# SCH_SLV262-__2026-06-26.net
KiCad netlist of a schematic drawn in EasyEDA
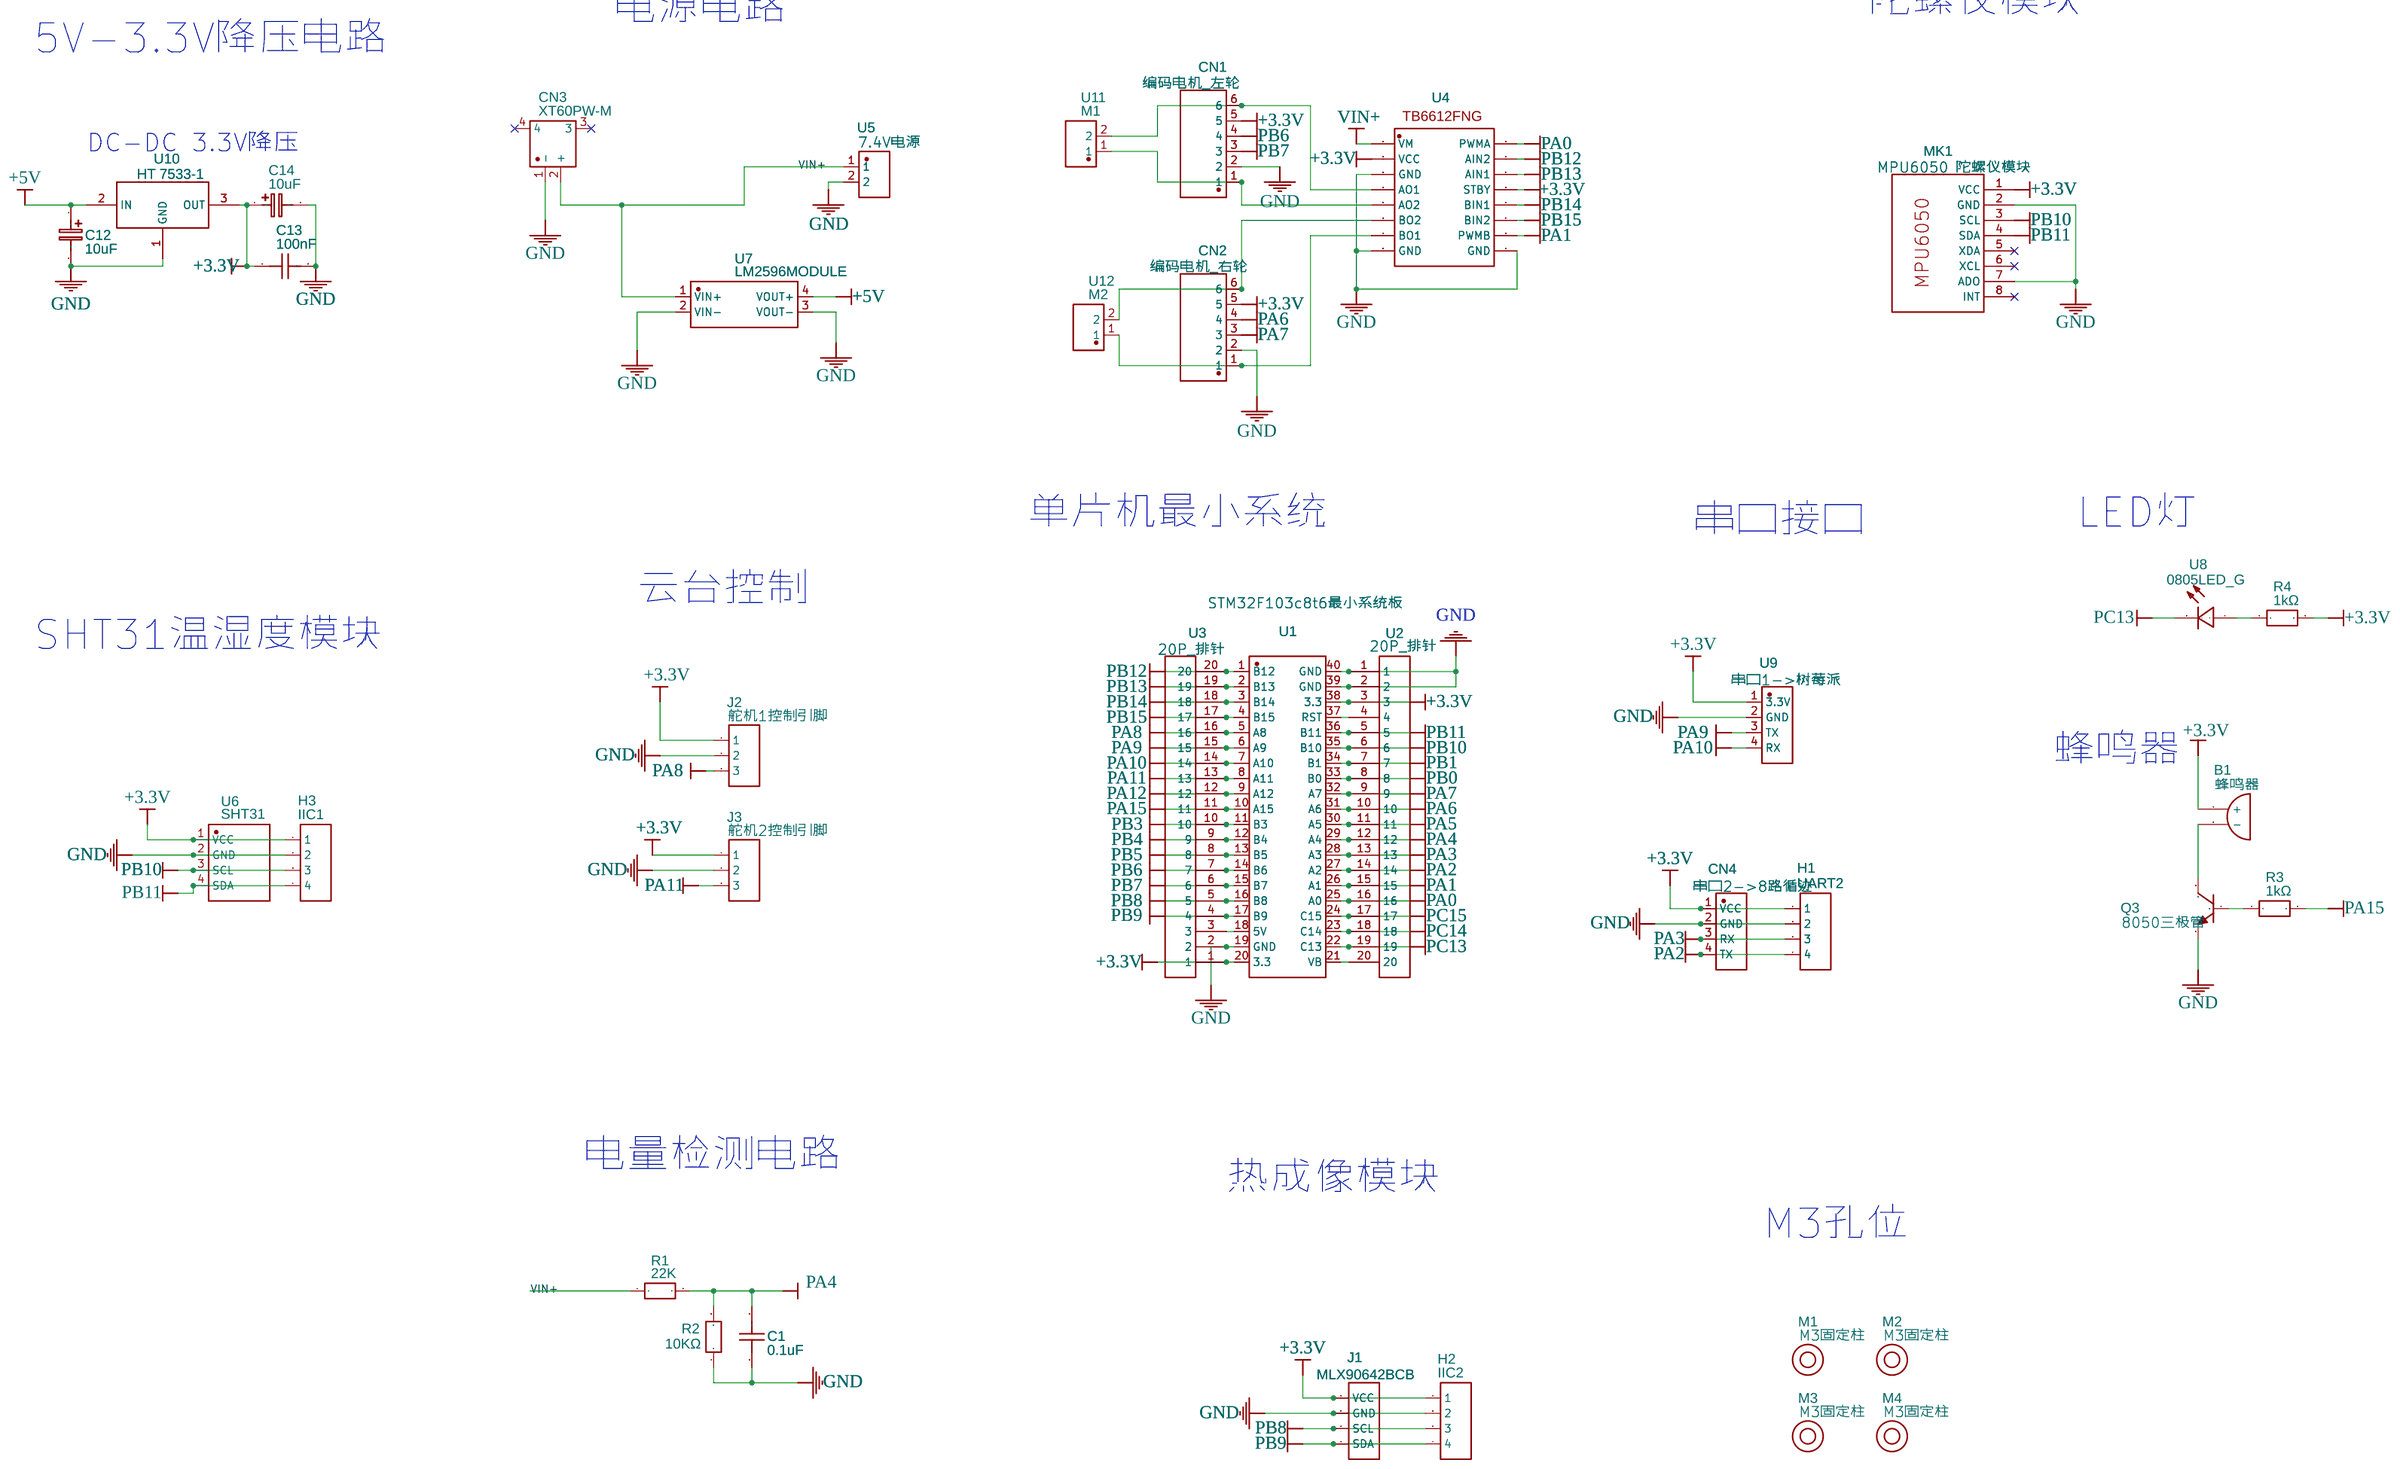
[diagram p0: schematic sheet]

(export (version "E")
  (design (tool "Eeschema 10.0.6"))
  (components
    (comp (ref "B1") (value "蜂鸣器") (libsource (lib "") (part "蜂鸣器")))
    (comp (ref "C1") (value "0.1uF") (libsource (lib "") (part "C_0603_US")))
    (comp (ref "C12") (value "10uF") (libsource (lib "") (part "C_Tan_SMD_A_EU_1")))
    (comp (ref "C13") (value "100nF") (libsource (lib "") (part "C_0603_US_1")))
    (comp (ref "C14") (value "10uF") (libsource (lib "") (part "C_Tan_SMD_A_EU")))
    (comp (ref "CN1")
      (value "编码电机_左轮")
      (fields (field (name "Manufacturer Part") "A2501WV-6P") (field (name "Manufacturer") "CJT(长江连接器)"))
      (libsource (lib "") (part "A2501WV-6P"))
    )
    (comp (ref "CN2")
      (value "编码电机_右轮")
      (fields (field (name "Manufacturer Part") "A2501WV-6P") (field (name "Manufacturer") "CJT(长江连接器)"))
      (libsource (lib "") (part "A2501WV-6P"))
    )
    (comp (ref "CN3")
      (value "XT60PW-M")
      (fields (field (name "Manufacturer") "AMASS(艾迈斯)"))
      (libsource (lib "") (part "XT60PW-M"))
    )
    (comp (ref "CN4")
      (value "串口2->8路循迹")
      (fields (field (name "Manufacturer Part") "HX-PH2.0-4PWZ") (field (name "Manufacturer") "hanxia(韩下)"))
      (libsource (lib "") (part "HX-PH2.0-4PWZ"))
    )
    (comp (ref "H1") (value "UART2") (libsource (lib "") (part "HDR-F-2.54_1x4")))
    (comp (ref "H2") (value "IIC2") (libsource (lib "") (part "HDR-F-2.54_1x4")))
    (comp (ref "H3") (value "IIC1") (libsource (lib "") (part "HDR-F-2.54_1x4")))
    (comp (ref "J1") (value "MLX90642BCB") (libsource (lib "") (part "HDR-M-2.54_1x4")))
    (comp (ref "J2") (value "舵机1控制引脚") (libsource (lib "") (part "HDR-M-2.54_1x3")))
    (comp (ref "J3") (value "舵机2控制引脚") (libsource (lib "") (part "HDR-M-2.54_1x3")))
    (comp (ref "M1") (value "M3固定柱") (libsource (lib "") (part "M3固定柱")))
    (comp (ref "M2") (value "M3固定柱") (libsource (lib "") (part "M3固定柱")))
    (comp (ref "M3") (value "M3固定柱") (libsource (lib "") (part "M3固定柱")))
    (comp (ref "M4") (value "M3固定柱") (libsource (lib "") (part "M3固定柱")))
    (comp (ref "MK1") (value "MPU6050 陀螺仪模块") (libsource (lib "") (part "MPU6050 陀螺仪模块")))
    (comp (ref "Q3")
      (value "8050三极管")
      (fields (field (name "Manufacturer Part") "SS8050DTA") (field (name "Manufacturer") "onsemi(安森美)"))
      (libsource (lib "") (part "8050三极管"))
    )
    (comp (ref "R1") (value "22K") (libsource (lib "") (part "R_0805_EU")))
    (comp (ref "R2") (value "10KΩ") (libsource (lib "") (part "R_0805_EU_1")))
    (comp (ref "R3")
      (value "1kΩ")
      (fields (field (name "Manufacturer Part") "PTFR0603B44K2N9") (field (name "Manufacturer") "RESI(开步睿思)"))
      (libsource (lib "") (part "R0603电阻"))
    )
    (comp (ref "R4")
      (value "1kΩ")
      (fields (field (name "Manufacturer Part") "PTFR0603B44K2N9") (field (name "Manufacturer") "RESI(开步睿思)"))
      (libsource (lib "") (part "R0603电阻"))
    )
    (comp (ref "U1") (value "STM32F103c8t6最小系统板") (libsource (lib "") (part "STM32F103c8t6最小系统板")))
    (comp (ref "U2") (value "20P_排针") (libsource (lib "") (part "20P排针")))
    (comp (ref "U3") (value "20P_排针") (libsource (lib "") (part "20P排针_1")))
    (comp (ref "U4") (value "TB6612") (libsource (lib "") (part "TB6612")))
    (comp (ref "U5")
      (value "7.4V电源")
      (fields (field (name "Manufacturer Part") "KF301-5.0-2P") (field (name "Manufacturer") "KEFA(科发)"))
      (libsource (lib "") (part "KF301-5.0-2P_1"))
    )
    (comp (ref "U6") (value "SHT31") (libsource (lib "") (part "SHT31")))
    (comp (ref "U7") (value "LM2596MODULE") (libsource (lib "") (part "LM2596MODULE")))
    (comp (ref "U8") (value "0805LED_G") (libsource (lib "") (part "0805LED_G")))
    (comp (ref "U9")
      (value "串口1->树莓派")
      (fields (field (name "Manufacturer Part") "XH2.54-4P- 直插"))
      (libsource (lib "") (part "XH2.54-4P- 直插"))
    )
    (comp (ref "U10") (value "HT 7533-1") (libsource (lib "") (part "HT 7533-1")))
    (comp (ref "U11")
      (value "M1")
      (fields (field (name "Manufacturer Part") "KF301-5.0-2P") (field (name "Manufacturer") "KEFA(科发)"))
      (libsource (lib "") (part "KF301-5.0-2P"))
    )
    (comp (ref "U12")
      (value "M2")
      (fields (field (name "Manufacturer Part") "KF301-5.0-2P") (field (name "Manufacturer") "KEFA(科发)"))
      (libsource (lib "") (part "KF301-5.0-2P"))
    )
  )
  (nets
    (net (code "1") (name "+3.3V") (class "Default")
      (node (ref "B1") (pin "1") (pinfunction "+_1") (pintype "unspecified"))
      (node (ref "C13") (pin "1") (pinfunction "1_1") (pintype "unspecified"))
      (node (ref "C14") (pin "1") (pinfunction "1_1") (pintype "unspecified"))
      (node (ref "CN1") (pin "5") (pinfunction "5_5") (pintype "unspecified"))
      (node (ref "CN2") (pin "5") (pinfunction "5_5") (pintype "unspecified"))
      (node (ref "CN4") (pin "1") (pinfunction "VCC_1") (pintype "unspecified"))
      (node (ref "H1") (pin "1") (pinfunction "1_1") (pintype "unspecified"))
      (node (ref "H2") (pin "1") (pinfunction "1_1") (pintype "unspecified"))
      (node (ref "H3") (pin "1") (pinfunction "1_1") (pintype "unspecified"))
      (node (ref "J1") (pin "1") (pinfunction "VCC_1") (pintype "unspecified"))
      (node (ref "J2") (pin "1") (pinfunction "1_1") (pintype "input"))
      (node (ref "J3") (pin "1") (pinfunction "1_1") (pintype "input"))
      (node (ref "MK1") (pin "1") (pinfunction "VCC_1") (pintype "unspecified"))
      (node (ref "R4") (pin "2") (pinfunction "2_2") (pintype "unspecified"))
      (node (ref "U1") (pin "20") (pinfunction "3.3_20") (pintype "unspecified"))
      (node (ref "U1") (pin "38") (pinfunction "3.3_38") (pintype "unspecified"))
      (node (ref "U10") (pin "3") (pinfunction "OUT_3") (pintype "unspecified"))
      (node (ref "U2") (pin "3") (pinfunction "3_3") (pintype "unspecified"))
      (node (ref "U3") (pin "1") (pinfunction "1_1") (pintype "unspecified"))
      (node (ref "U4") (pin "13") (pinfunction "STBY_13") (pintype "unspecified"))
      (node (ref "U4") (pin "2") (pinfunction "VCC_2") (pintype "unspecified"))
      (node (ref "U6") (pin "1") (pinfunction "VCC_1") (pintype "unspecified"))
      (node (ref "U9") (pin "1") (pinfunction "3.3V_1") (pintype "unspecified"))
    )
    (net (code "2") (name "+5V") (class "Default")
      (node (ref "C12") (pin "1") (pinfunction "1_1") (pintype "unspecified"))
      (node (ref "U10") (pin "2") (pinfunction "IN_2") (pintype "unspecified"))
      (node (ref "U7") (pin "4") (pinfunction "VOUT+_4") (pintype "unspecified"))
    )
    (net (code "3") (name "GND") (class "Default")
      (node (ref "C1") (pin "1") (pinfunction "1_1") (pintype "unspecified"))
      (node (ref "C12") (pin "2") (pinfunction "2_2") (pintype "unspecified"))
      (node (ref "C13") (pin "2") (pinfunction "2_2") (pintype "unspecified"))
      (node (ref "C14") (pin "2") (pinfunction "2_2") (pintype "unspecified"))
      (node (ref "CN1") (pin "2") (pinfunction "2_2") (pintype "unspecified"))
      (node (ref "CN2") (pin "2") (pinfunction "2_2") (pintype "unspecified"))
      (node (ref "CN3") (pin "1") (pinfunction "-_1") (pintype "unspecified"))
      (node (ref "CN4") (pin "2") (pinfunction "GND_2") (pintype "unspecified"))
      (node (ref "H1") (pin "2") (pinfunction "2_2") (pintype "unspecified"))
      (node (ref "H2") (pin "2") (pinfunction "2_2") (pintype "unspecified"))
      (node (ref "H3") (pin "2") (pinfunction "2_2") (pintype "unspecified"))
      (node (ref "J1") (pin "2") (pinfunction "GND_2") (pintype "unspecified"))
      (node (ref "J2") (pin "2") (pinfunction "2_2") (pintype "input"))
      (node (ref "J3") (pin "2") (pinfunction "2_2") (pintype "input"))
      (node (ref "MK1") (pin "2") (pinfunction "GND_2") (pintype "unspecified"))
      (node (ref "MK1") (pin "7") (pinfunction "ADO_7") (pintype "unspecified"))
      (node (ref "Q3") (pin "1") (pinfunction "E_1") (pintype "unspecified"))
      (node (ref "R2") (pin "1") (pinfunction "1_1") (pintype "unspecified"))
      (node (ref "U1") (pin "19") (pinfunction "GND_19") (pintype "unspecified"))
      (node (ref "U1") (pin "39") (pinfunction "GND_39") (pintype "unspecified"))
      (node (ref "U1") (pin "40") (pinfunction "GND_40") (pintype "unspecified"))
      (node (ref "U10") (pin "1") (pinfunction "GND_1") (pintype "unspecified"))
      (node (ref "U2") (pin "1") (pinfunction "1_1") (pintype "unspecified"))
      (node (ref "U2") (pin "2") (pinfunction "2_2") (pintype "unspecified"))
      (node (ref "U3") (pin "2") (pinfunction "2_2") (pintype "unspecified"))
      (node (ref "U4") (pin "3") (pinfunction "GND_3") (pintype "unspecified"))
      (node (ref "U4") (pin "8") (pinfunction "GND_8") (pintype "unspecified"))
      (node (ref "U4") (pin "9") (pinfunction "GND_9") (pintype "unspecified"))
      (node (ref "U5") (pin "2") (pinfunction "2_2") (pintype "unspecified"))
      (node (ref "U6") (pin "2") (pinfunction "GND_2") (pintype "unspecified"))
      (node (ref "U7") (pin "2") (pinfunction "VIN-_2") (pintype "unspecified"))
      (node (ref "U7") (pin "3") (pinfunction "VOUT-_3") (pintype "unspecified"))
      (node (ref "U9") (pin "2") (pinfunction "GND_2") (pintype "unspecified"))
    )
    (net (code "4") (name "Net-(B1--)") (class "Default")
      (node (ref "B1") (pin "2") (pinfunction "-_2") (pintype "unspecified"))
      (node (ref "Q3") (pin "3") (pinfunction "C_3") (pintype "unspecified"))
    )
    (net (code "5") (name "Net-(Q3-B)") (class "Default")
      (node (ref "Q3") (pin "2") (pinfunction "B_2") (pintype "unspecified"))
      (node (ref "R3") (pin "1") (pinfunction "1_1") (pintype "unspecified"))
    )
    (net (code "6") (name "Net-(U1-5V)") (class "Default")
      (node (ref "U1") (pin "18") (pinfunction "5V_18") (pintype "unspecified"))
      (node (ref "U3") (pin "3") (pinfunction "3_3") (pintype "unspecified"))
    )
    (net (code "7") (name "Net-(U1-RST)") (class "Default")
      (node (ref "U1") (pin "37") (pinfunction "RST_37") (pintype "unspecified"))
      (node (ref "U2") (pin "4") (pinfunction "4_4") (pintype "unspecified"))
    )
    (net (code "8") (name "Net-(U1-VB)") (class "Default")
      (node (ref "U1") (pin "21") (pinfunction "VB_21") (pintype "unspecified"))
      (node (ref "U2") (pin "20") (pinfunction "20_20") (pintype "unspecified"))
    )
    (net (code "9") (name "Net-(U4-AO1)") (class "Default")
      (node (ref "CN1") (pin "6") (pinfunction "6_6") (pintype "unspecified"))
      (node (ref "U11") (pin "2") (pinfunction "2_2") (pintype "unspecified"))
      (node (ref "U4") (pin "4") (pinfunction "AO1_4") (pintype "unspecified"))
    )
    (net (code "10") (name "Net-(U4-AO2)") (class "Default")
      (node (ref "CN1") (pin "1") (pinfunction "1_1") (pintype "unspecified"))
      (node (ref "U11") (pin "1") (pinfunction "1_1") (pintype "unspecified"))
      (node (ref "U4") (pin "5") (pinfunction "AO2_5") (pintype "unspecified"))
    )
    (net (code "11") (name "Net-(U4-BO1)") (class "Default")
      (node (ref "CN2") (pin "1") (pinfunction "1_1") (pintype "unspecified"))
      (node (ref "U12") (pin "1") (pinfunction "1_1") (pintype "unspecified"))
      (node (ref "U4") (pin "7") (pinfunction "BO1_7") (pintype "unspecified"))
    )
    (net (code "12") (name "Net-(U4-BO2)") (class "Default")
      (node (ref "CN2") (pin "6") (pinfunction "6_6") (pintype "unspecified"))
      (node (ref "U12") (pin "2") (pinfunction "2_2") (pintype "unspecified"))
      (node (ref "U4") (pin "6") (pinfunction "BO2_6") (pintype "unspecified"))
    )
    (net (code "13") (name "Net-(U8-+)") (class "Default")
      (node (ref "R4") (pin "1") (pinfunction "1_1") (pintype "unspecified"))
      (node (ref "U8") (pin "1") (pinfunction "+_1") (pintype "unspecified"))
    )
    (net (code "14") (name "PA0") (class "Default")
      (node (ref "U1") (pin "25") (pinfunction "A0_25") (pintype "unspecified"))
      (node (ref "U2") (pin "16") (pinfunction "16_16") (pintype "unspecified"))
      (node (ref "U4") (pin "16") (pinfunction "PWMA_16") (pintype "unspecified"))
    )
    (net (code "15") (name "PA1") (class "Default")
      (node (ref "U1") (pin "26") (pinfunction "A1_26") (pintype "unspecified"))
      (node (ref "U2") (pin "15") (pinfunction "15_15") (pintype "unspecified"))
      (node (ref "U4") (pin "10") (pinfunction "PWMB_10") (pintype "unspecified"))
    )
    (net (code "16") (name "PA2") (class "Default")
      (node (ref "CN4") (pin "4") (pinfunction "TX_4") (pintype "unspecified"))
      (node (ref "H1") (pin "4") (pinfunction "4_4") (pintype "unspecified"))
      (node (ref "U1") (pin "27") (pinfunction "A2_27") (pintype "unspecified"))
      (node (ref "U2") (pin "14") (pinfunction "14_14") (pintype "unspecified"))
    )
    (net (code "17") (name "PA3") (class "Default")
      (node (ref "CN4") (pin "3") (pinfunction "RX_3") (pintype "unspecified"))
      (node (ref "H1") (pin "3") (pinfunction "3_3") (pintype "unspecified"))
      (node (ref "U1") (pin "28") (pinfunction "A3_28") (pintype "unspecified"))
      (node (ref "U2") (pin "13") (pinfunction "13_13") (pintype "unspecified"))
    )
    (net (code "18") (name "PA4") (class "Default")
      (node (ref "C1") (pin "2") (pinfunction "2_2") (pintype "unspecified"))
      (node (ref "R1") (pin "2") (pinfunction "2_2") (pintype "unspecified"))
      (node (ref "R2") (pin "2") (pinfunction "2_2") (pintype "unspecified"))
      (node (ref "U1") (pin "29") (pinfunction "A4_29") (pintype "unspecified"))
      (node (ref "U2") (pin "12") (pinfunction "12_12") (pintype "unspecified"))
    )
    (net (code "19") (name "PA5") (class "Default")
      (node (ref "U1") (pin "30") (pinfunction "A5_30") (pintype "unspecified"))
      (node (ref "U2") (pin "11") (pinfunction "11_11") (pintype "unspecified"))
    )
    (net (code "20") (name "PA6") (class "Default")
      (node (ref "CN2") (pin "4") (pinfunction "4_4") (pintype "unspecified"))
      (node (ref "U1") (pin "31") (pinfunction "A6_31") (pintype "unspecified"))
      (node (ref "U2") (pin "10") (pinfunction "10_10") (pintype "unspecified"))
    )
    (net (code "21") (name "PA7") (class "Default")
      (node (ref "CN2") (pin "3") (pinfunction "3_3") (pintype "unspecified"))
      (node (ref "U1") (pin "32") (pinfunction "A7_32") (pintype "unspecified"))
      (node (ref "U2") (pin "9") (pinfunction "9_9") (pintype "unspecified"))
    )
    (net (code "22") (name "PA8") (class "Default")
      (node (ref "J2") (pin "3") (pinfunction "3_3") (pintype "input"))
      (node (ref "U1") (pin "5") (pinfunction "A8_5") (pintype "unspecified"))
      (node (ref "U3") (pin "16") (pinfunction "16_16") (pintype "unspecified"))
    )
    (net (code "23") (name "PA9") (class "Default")
      (node (ref "U1") (pin "6") (pinfunction "A9_6") (pintype "unspecified"))
      (node (ref "U3") (pin "15") (pinfunction "15_15") (pintype "unspecified"))
      (node (ref "U9") (pin "3") (pinfunction "TX_3") (pintype "unspecified"))
    )
    (net (code "24") (name "PA10") (class "Default")
      (node (ref "U1") (pin "7") (pinfunction "A10_7") (pintype "unspecified"))
      (node (ref "U3") (pin "14") (pinfunction "14_14") (pintype "unspecified"))
      (node (ref "U9") (pin "4") (pinfunction "RX_4") (pintype "unspecified"))
    )
    (net (code "25") (name "PA11") (class "Default")
      (node (ref "J3") (pin "3") (pinfunction "3_3") (pintype "input"))
      (node (ref "U1") (pin "8") (pinfunction "A11_8") (pintype "unspecified"))
      (node (ref "U3") (pin "13") (pinfunction "13_13") (pintype "unspecified"))
    )
    (net (code "26") (name "PA12") (class "Default")
      (node (ref "U1") (pin "9") (pinfunction "A12_9") (pintype "unspecified"))
      (node (ref "U3") (pin "12") (pinfunction "12_12") (pintype "unspecified"))
    )
    (net (code "27") (name "PA15") (class "Default")
      (node (ref "R3") (pin "2") (pinfunction "2_2") (pintype "unspecified"))
      (node (ref "U1") (pin "10") (pinfunction "A15_10") (pintype "unspecified"))
      (node (ref "U3") (pin "11") (pinfunction "11_11") (pintype "unspecified"))
    )
    (net (code "28") (name "PB0") (class "Default")
      (node (ref "U1") (pin "33") (pinfunction "B0_33") (pintype "unspecified"))
      (node (ref "U2") (pin "8") (pinfunction "8_8") (pintype "unspecified"))
    )
    (net (code "29") (name "PB1") (class "Default")
      (node (ref "U1") (pin "34") (pinfunction "B1_34") (pintype "unspecified"))
      (node (ref "U2") (pin "7") (pinfunction "7_7") (pintype "unspecified"))
    )
    (net (code "30") (name "PB3") (class "Default")
      (node (ref "U1") (pin "11") (pinfunction "B3_11") (pintype "unspecified"))
      (node (ref "U3") (pin "10") (pinfunction "10_10") (pintype "unspecified"))
    )
    (net (code "31") (name "PB4") (class "Default")
      (node (ref "U1") (pin "12") (pinfunction "B4_12") (pintype "unspecified"))
      (node (ref "U3") (pin "9") (pinfunction "9_9") (pintype "unspecified"))
    )
    (net (code "32") (name "PB5") (class "Default")
      (node (ref "U1") (pin "13") (pinfunction "B5_13") (pintype "unspecified"))
      (node (ref "U3") (pin "8") (pinfunction "8_8") (pintype "unspecified"))
    )
    (net (code "33") (name "PB6") (class "Default")
      (node (ref "CN1") (pin "4") (pinfunction "4_4") (pintype "unspecified"))
      (node (ref "U1") (pin "14") (pinfunction "B6_14") (pintype "unspecified"))
      (node (ref "U3") (pin "7") (pinfunction "7_7") (pintype "unspecified"))
    )
    (net (code "34") (name "PB7") (class "Default")
      (node (ref "CN1") (pin "3") (pinfunction "3_3") (pintype "unspecified"))
      (node (ref "U1") (pin "15") (pinfunction "B7_15") (pintype "unspecified"))
      (node (ref "U3") (pin "6") (pinfunction "6_6") (pintype "unspecified"))
    )
    (net (code "35") (name "PB8") (class "Default")
      (node (ref "H2") (pin "3") (pinfunction "3_3") (pintype "unspecified"))
      (node (ref "J1") (pin "3") (pinfunction "SCL_3") (pintype "unspecified"))
      (node (ref "U1") (pin "16") (pinfunction "B8_16") (pintype "unspecified"))
      (node (ref "U3") (pin "5") (pinfunction "5_5") (pintype "unspecified"))
    )
    (net (code "36") (name "PB9") (class "Default")
      (node (ref "H2") (pin "4") (pinfunction "4_4") (pintype "unspecified"))
      (node (ref "J1") (pin "4") (pinfunction "SDA_4") (pintype "unspecified"))
      (node (ref "U1") (pin "17") (pinfunction "B9_17") (pintype "unspecified"))
      (node (ref "U3") (pin "4") (pinfunction "4_4") (pintype "unspecified"))
    )
    (net (code "37") (name "PB10") (class "Default")
      (node (ref "H3") (pin "3") (pinfunction "3_3") (pintype "unspecified"))
      (node (ref "MK1") (pin "3") (pinfunction "SCL_3") (pintype "unspecified"))
      (node (ref "U1") (pin "35") (pinfunction "B10_35") (pintype "unspecified"))
      (node (ref "U2") (pin "6") (pinfunction "6_6") (pintype "unspecified"))
      (node (ref "U6") (pin "3") (pinfunction "SCL_3") (pintype "unspecified"))
    )
    (net (code "38") (name "PB11") (class "Default")
      (node (ref "H3") (pin "4") (pinfunction "4_4") (pintype "unspecified"))
      (node (ref "MK1") (pin "4") (pinfunction "SDA_4") (pintype "unspecified"))
      (node (ref "U1") (pin "36") (pinfunction "B11_36") (pintype "unspecified"))
      (node (ref "U2") (pin "5") (pinfunction "5_5") (pintype "unspecified"))
      (node (ref "U6") (pin "4") (pinfunction "SDA_4") (pintype "unspecified"))
    )
    (net (code "39") (name "PB12") (class "Default")
      (node (ref "U1") (pin "1") (pinfunction "B12_1") (pintype "unspecified"))
      (node (ref "U3") (pin "20") (pinfunction "20_20") (pintype "unspecified"))
      (node (ref "U4") (pin "15") (pinfunction "AIN2_15") (pintype "unspecified"))
    )
    (net (code "40") (name "PB13") (class "Default")
      (node (ref "U1") (pin "2") (pinfunction "B13_2") (pintype "unspecified"))
      (node (ref "U3") (pin "19") (pinfunction "19_19") (pintype "unspecified"))
      (node (ref "U4") (pin "14") (pinfunction "AIN1_14") (pintype "unspecified"))
    )
    (net (code "41") (name "PB14") (class "Default")
      (node (ref "U1") (pin "3") (pinfunction "B14_3") (pintype "unspecified"))
      (node (ref "U3") (pin "18") (pinfunction "18_18") (pintype "unspecified"))
      (node (ref "U4") (pin "12") (pinfunction "BIN1_12") (pintype "unspecified"))
    )
    (net (code "42") (name "PB15") (class "Default")
      (node (ref "U1") (pin "4") (pinfunction "B15_4") (pintype "unspecified"))
      (node (ref "U3") (pin "17") (pinfunction "17_17") (pintype "unspecified"))
      (node (ref "U4") (pin "11") (pinfunction "BIN2_11") (pintype "unspecified"))
    )
    (net (code "43") (name "PC13") (class "Default")
      (node (ref "U1") (pin "22") (pinfunction "C13_22") (pintype "unspecified"))
      (node (ref "U2") (pin "19") (pinfunction "19_19") (pintype "unspecified"))
      (node (ref "U8") (pin "2") (pinfunction "-_2") (pintype "unspecified"))
    )
    (net (code "44") (name "PC14") (class "Default")
      (node (ref "U1") (pin "23") (pinfunction "C14_23") (pintype "unspecified"))
      (node (ref "U2") (pin "18") (pinfunction "18_18") (pintype "unspecified"))
    )
    (net (code "45") (name "PC15") (class "Default")
      (node (ref "U1") (pin "24") (pinfunction "C15_24") (pintype "unspecified"))
      (node (ref "U2") (pin "17") (pinfunction "17_17") (pintype "unspecified"))
    )
    (net (code "46") (name "VIN+") (class "Default")
      (node (ref "CN3") (pin "2") (pinfunction "+_2") (pintype "unspecified"))
      (node (ref "R1") (pin "1") (pinfunction "1_1") (pintype "unspecified"))
      (node (ref "U4") (pin "1") (pinfunction "VM_1") (pintype "unspecified"))
      (node (ref "U5") (pin "1") (pinfunction "1_1") (pintype "unspecified"))
      (node (ref "U7") (pin "1") (pinfunction "VIN+_1") (pintype "unspecified"))
    )
    (net (code "47") (name "unconnected-(CN3-Pad3)") (class "Default")
      (node (ref "CN3") (pin "3") (pinfunction "3_3") (pintype "unspecified+no_connect"))
    )
    (net (code "48") (name "unconnected-(CN3-Pad4)") (class "Default")
      (node (ref "CN3") (pin "4") (pinfunction "4_4") (pintype "unspecified+no_connect"))
    )
    (net (code "49") (name "unconnected-(MK1-INT-Pad8)") (class "Default")
      (node (ref "MK1") (pin "8") (pinfunction "INT_8") (pintype "unspecified+no_connect"))
    )
    (net (code "50") (name "unconnected-(MK1-XCL-Pad6)") (class "Default")
      (node (ref "MK1") (pin "6") (pinfunction "XCL_6") (pintype "unspecified+no_connect"))
    )
    (net (code "51") (name "unconnected-(MK1-XDA-Pad5)") (class "Default")
      (node (ref "MK1") (pin "5") (pinfunction "XDA_5") (pintype "unspecified+no_connect"))
    )
  )
)
